# odd_v1.net
KiCad netlist of a schematic drawn in EAGLE
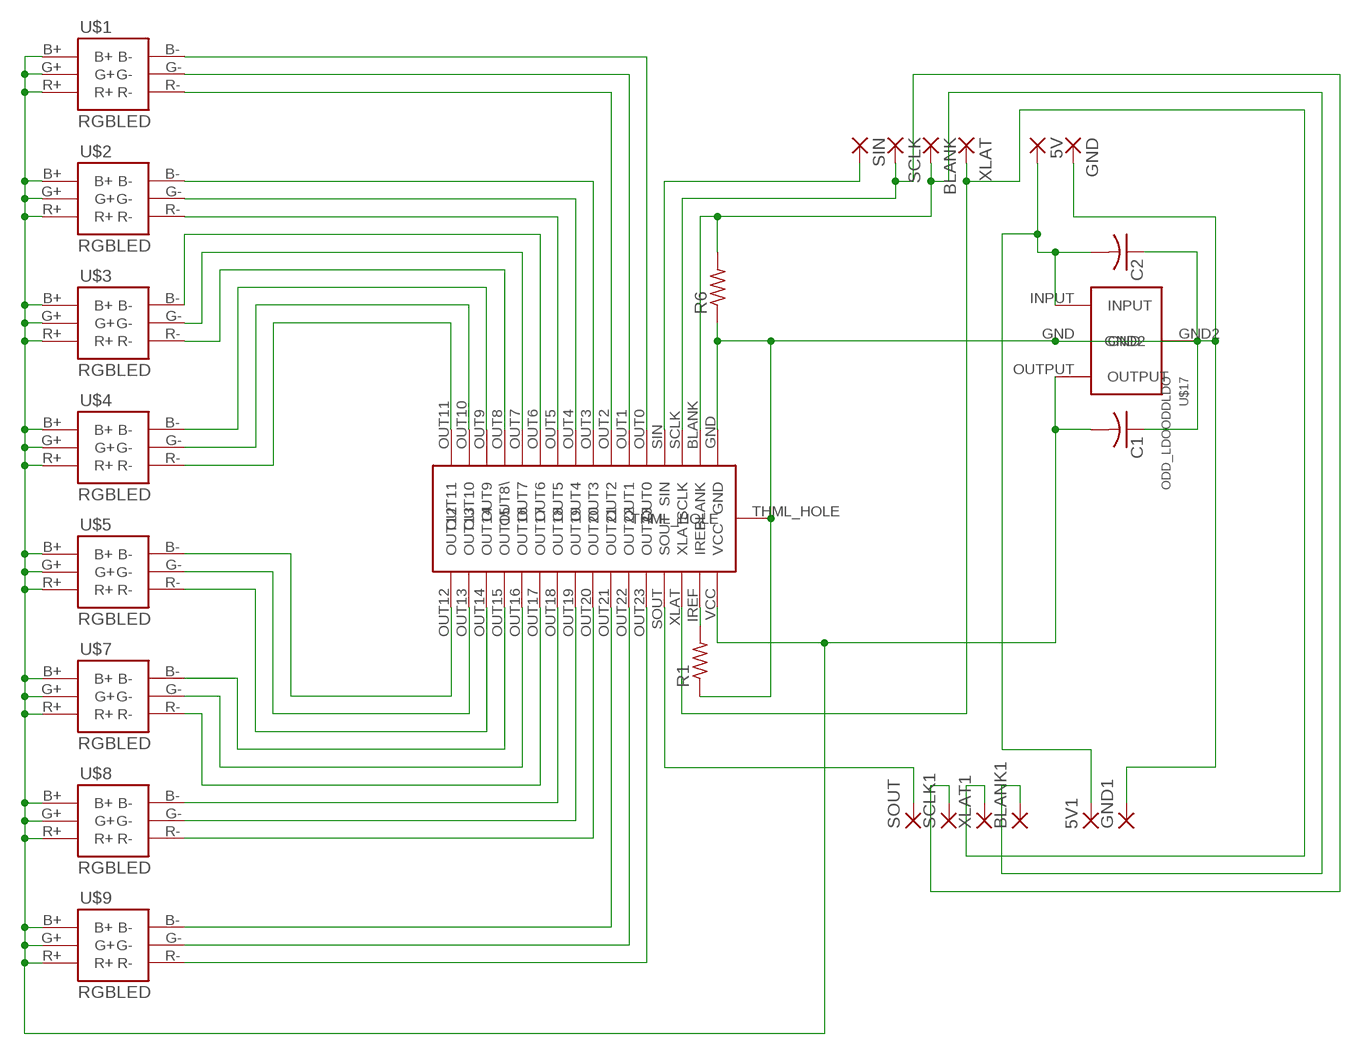
[diagram p0: schematic, sheet 1]

(export (version "E")
  (design (tool "Eeschema 10.0.6"))
  (components
    (comp (ref "5V")
      (value "2,54/1,1")
      (footprint "eagle-import:2,54_1,1")
      (libsource (lib "eagle-import") (part "2,54/1,1"))
    )
    (comp (ref "5V1")
      (value "2,54/1,1")
      (footprint "eagle-import:2,54_1,1")
      (libsource (lib "eagle-import") (part "2,54/1,1"))
    )
    (comp (ref "BLANK")
      (value "2,54/1,1")
      (footprint "eagle-import:2,54_1,1")
      (libsource (lib "eagle-import") (part "2,54/1,1"))
    )
    (comp (ref "BLANK1")
      (value "2,54/1,1")
      (footprint "eagle-import:2,54_1,1")
      (libsource (lib "eagle-import") (part "2,54/1,1"))
    )
    (comp (ref "C1")
      (value "C-US050-025X075")
      (footprint "eagle-import:C050-025X075")
      (libsource (lib "eagle-import") (part "C-US050-025X075"))
    )
    (comp (ref "C2")
      (value "C-US050-025X075")
      (footprint "eagle-import:C050-025X075")
      (libsource (lib "eagle-import") (part "C-US050-025X075"))
    )
    (comp (ref "GND")
      (value "2,54/1,1")
      (footprint "eagle-import:2,54_1,1")
      (libsource (lib "eagle-import") (part "2,54/1,1"))
    )
    (comp (ref "GND1")
      (value "2,54/1,1")
      (footprint "eagle-import:2,54_1,1")
      (libsource (lib "eagle-import") (part "2,54/1,1"))
    )
    (comp (ref "R1")
      (value "R-US_0204/7")
      (footprint "eagle-import:0204_7")
      (libsource (lib "eagle-import") (part "R-US_0204/7"))
    )
    (comp (ref "R6")
      (value "R-US_0204/7")
      (footprint "eagle-import:0204_7")
      (libsource (lib "eagle-import") (part "R-US_0204/7"))
    )
    (comp (ref "SCLK")
      (value "2,54/1,1")
      (footprint "eagle-import:2,54_1,1")
      (libsource (lib "eagle-import") (part "2,54/1,1"))
    )
    (comp (ref "SCLK1")
      (value "2,54/1,1")
      (footprint "eagle-import:2,54_1,1")
      (libsource (lib "eagle-import") (part "2,54/1,1"))
    )
    (comp (ref "SIN")
      (value "2,54/1,1")
      (footprint "eagle-import:2,54_1,1")
      (libsource (lib "eagle-import") (part "2,54/1,1"))
    )
    (comp (ref "SOUT")
      (value "2,54/1,1")
      (footprint "eagle-import:2,54_1,1")
      (libsource (lib "eagle-import") (part "2,54/1,1"))
    )
    (comp (ref "U$1")
      (value "RGBLED")
      (footprint "eagle-import:6PADSMD")
      (libsource (lib "eagle-import") (part "CREESMDRGBLED6PADSMD"))
    )
    (comp (ref "U$2")
      (value "RGBLED")
      (footprint "eagle-import:6PADSMD")
      (libsource (lib "eagle-import") (part "CREESMDRGBLED6PADSMD"))
    )
    (comp (ref "U$3")
      (value "RGBLED")
      (footprint "eagle-import:6PADSMD")
      (libsource (lib "eagle-import") (part "CREESMDRGBLED6PADSMD"))
    )
    (comp (ref "U$4")
      (value "RGBLED")
      (footprint "eagle-import:6PADSMD")
      (libsource (lib "eagle-import") (part "CREESMDRGBLED6PADSMD"))
    )
    (comp (ref "U$5")
      (value "RGBLED")
      (footprint "eagle-import:6PADSMD")
      (libsource (lib "eagle-import") (part "CREESMDRGBLED6PADSMD"))
    )
    (comp (ref "U$6")
      (value "TLC5947")
      (footprint "eagle-import:32_SMD")
      (libsource (lib "eagle-import") (part "TLC5947"))
    )
    (comp (ref "U$7")
      (value "RGBLED")
      (footprint "eagle-import:6PADSMD")
      (libsource (lib "eagle-import") (part "CREESMDRGBLED6PADSMD"))
    )
    (comp (ref "U$8")
      (value "RGBLED")
      (footprint "eagle-import:6PADSMD")
      (libsource (lib "eagle-import") (part "CREESMDRGBLED6PADSMD"))
    )
    (comp (ref "U$9")
      (value "RGBLED")
      (footprint "eagle-import:6PADSMD")
      (libsource (lib "eagle-import") (part "CREESMDRGBLED6PADSMD"))
    )
    (comp (ref "U$17")
      (value "ODD_LDOODDLDO")
      (footprint "eagle-import:4PINLDO")
      (libsource (lib "eagle-import") (part "ODD_LDOODDLDO"))
    )
    (comp (ref "XLAT")
      (value "2,54/1,1")
      (footprint "eagle-import:2,54_1,1")
      (libsource (lib "eagle-import") (part "2,54/1,1"))
    )
    (comp (ref "XLAT1")
      (value "2,54/1,1")
      (footprint "eagle-import:2,54_1,1")
      (libsource (lib "eagle-import") (part "2,54/1,1"))
    )
  )
  (nets
    (net (code "1") (name "Net-(5V-P)") (class "Default")
      (node (ref "5V") (pin "1") (pinfunction "P_1") (pintype "passive"))
      (node (ref "5V1") (pin "1") (pinfunction "P_1") (pintype "passive"))
      (node (ref "C2") (pin "2") (pinfunction "2_2") (pintype "passive"))
      (node (ref "U$17") (pin "INPUT") (pinfunction "INPUT_INPUT") (pintype "bidirectional"))
    )
    (net (code "2") (name "Net-(BLANK-P)") (class "Default")
      (node (ref "BLANK") (pin "1") (pinfunction "P_1") (pintype "passive"))
      (node (ref "BLANK1") (pin "1") (pinfunction "P_1") (pintype "passive"))
      (node (ref "R6") (pin "2") (pinfunction "2_2") (pintype "passive"))
      (node (ref "U$6") (pin "BLANK") (pinfunction "BLANK_BLANK") (pintype "bidirectional"))
    )
    (net (code "3") (name "Net-(C1-Pad2)") (class "Default")
      (node (ref "C1") (pin "2") (pinfunction "2_2") (pintype "passive"))
      (node (ref "U$1") (pin "B+") (pinfunction "B+_B+") (pintype "bidirectional"))
      (node (ref "U$1") (pin "G+") (pinfunction "G+_G+") (pintype "bidirectional"))
      (node (ref "U$1") (pin "R+") (pinfunction "R+_R+") (pintype "bidirectional"))
      (node (ref "U$17") (pin "OUTPUT") (pinfunction "OUTPUT_OUTPUT") (pintype "bidirectional"))
      (node (ref "U$2") (pin "B+") (pinfunction "B+_B+") (pintype "bidirectional"))
      (node (ref "U$2") (pin "G+") (pinfunction "G+_G+") (pintype "bidirectional"))
      (node (ref "U$2") (pin "R+") (pinfunction "R+_R+") (pintype "bidirectional"))
      (node (ref "U$3") (pin "B+") (pinfunction "B+_B+") (pintype "bidirectional"))
      (node (ref "U$3") (pin "G+") (pinfunction "G+_G+") (pintype "bidirectional"))
      (node (ref "U$3") (pin "R+") (pinfunction "R+_R+") (pintype "bidirectional"))
      (node (ref "U$4") (pin "B+") (pinfunction "B+_B+") (pintype "bidirectional"))
      (node (ref "U$4") (pin "G+") (pinfunction "G+_G+") (pintype "bidirectional"))
      (node (ref "U$4") (pin "R+") (pinfunction "R+_R+") (pintype "bidirectional"))
      (node (ref "U$5") (pin "B+") (pinfunction "B+_B+") (pintype "bidirectional"))
      (node (ref "U$5") (pin "G+") (pinfunction "G+_G+") (pintype "bidirectional"))
      (node (ref "U$5") (pin "R+") (pinfunction "R+_R+") (pintype "bidirectional"))
      (node (ref "U$6") (pin "VCC") (pinfunction "VCC_VCC") (pintype "bidirectional"))
      (node (ref "U$7") (pin "B+") (pinfunction "B+_B+") (pintype "bidirectional"))
      (node (ref "U$7") (pin "G+") (pinfunction "G+_G+") (pintype "bidirectional"))
      (node (ref "U$7") (pin "R+") (pinfunction "R+_R+") (pintype "bidirectional"))
      (node (ref "U$8") (pin "B+") (pinfunction "B+_B+") (pintype "bidirectional"))
      (node (ref "U$8") (pin "G+") (pinfunction "G+_G+") (pintype "bidirectional"))
      (node (ref "U$8") (pin "R+") (pinfunction "R+_R+") (pintype "bidirectional"))
      (node (ref "U$9") (pin "B+") (pinfunction "B+_B+") (pintype "bidirectional"))
      (node (ref "U$9") (pin "G+") (pinfunction "G+_G+") (pintype "bidirectional"))
      (node (ref "U$9") (pin "R+") (pinfunction "R+_R+") (pintype "bidirectional"))
    )
    (net (code "4") (name "Net-(GND-P)") (class "Default")
      (node (ref "C1") (pin "1") (pinfunction "1_1") (pintype "passive"))
      (node (ref "C2") (pin "1") (pinfunction "1_1") (pintype "passive"))
      (node (ref "GND") (pin "1") (pinfunction "P_1") (pintype "passive"))
      (node (ref "GND1") (pin "1") (pinfunction "P_1") (pintype "passive"))
      (node (ref "R1") (pin "1") (pinfunction "1_1") (pintype "passive"))
      (node (ref "R6") (pin "1") (pinfunction "1_1") (pintype "passive"))
      (node (ref "U$17") (pin "GND") (pinfunction "GND_GND") (pintype "bidirectional"))
      (node (ref "U$17") (pin "GND2") (pinfunction "GND2_GND2") (pintype "bidirectional"))
      (node (ref "U$6") (pin "GND") (pinfunction "GND_GND") (pintype "bidirectional"))
      (node (ref "U$6") (pin "THML_HOLE") (pinfunction "THML_HOLE_THML_HOLE") (pintype "bidirectional"))
    )
    (net (code "5") (name "Net-(R1-Pad2)") (class "Default")
      (node (ref "R1") (pin "2") (pinfunction "2_2") (pintype "passive"))
      (node (ref "U$6") (pin "IREF") (pinfunction "IREF_IREF") (pintype "bidirectional"))
    )
    (net (code "6") (name "Net-(SCLK-P)") (class "Default")
      (node (ref "SCLK") (pin "1") (pinfunction "P_1") (pintype "passive"))
      (node (ref "SCLK1") (pin "1") (pinfunction "P_1") (pintype "passive"))
      (node (ref "U$6") (pin "SCLK") (pinfunction "SCLK_SCLK") (pintype "bidirectional"))
    )
    (net (code "7") (name "Net-(SIN-P)") (class "Default")
      (node (ref "SIN") (pin "1") (pinfunction "P_1") (pintype "passive"))
      (node (ref "U$6") (pin "SIN") (pinfunction "SIN_SIN") (pintype "bidirectional"))
    )
    (net (code "8") (name "Net-(SOUT-P)") (class "Default")
      (node (ref "SOUT") (pin "1") (pinfunction "P_1") (pintype "passive"))
      (node (ref "U$6") (pin "SOUT") (pinfunction "SOUT_SOUT") (pintype "bidirectional"))
    )
    (net (code "9") (name "Net-(U$1-PadB-)") (class "Default")
      (node (ref "U$1") (pin "B-") (pinfunction "B-_B-") (pintype "bidirectional"))
      (node (ref "U$6") (pin "OUT0") (pinfunction "OUT0_OUT0") (pintype "bidirectional"))
    )
    (net (code "10") (name "Net-(U$1-PadG-)") (class "Default")
      (node (ref "U$1") (pin "G-") (pinfunction "G-_G-") (pintype "bidirectional"))
      (node (ref "U$6") (pin "OUT1") (pinfunction "OUT1_OUT1") (pintype "bidirectional"))
    )
    (net (code "11") (name "Net-(U$1-PadR-)") (class "Default")
      (node (ref "U$1") (pin "R-") (pinfunction "R-_R-") (pintype "bidirectional"))
      (node (ref "U$6") (pin "OUT2") (pinfunction "OUT2_OUT2") (pintype "bidirectional"))
    )
    (net (code "12") (name "Net-(U$2-PadB-)") (class "Default")
      (node (ref "U$2") (pin "B-") (pinfunction "B-_B-") (pintype "bidirectional"))
      (node (ref "U$6") (pin "OUT3") (pinfunction "OUT3_OUT3") (pintype "bidirectional"))
    )
    (net (code "13") (name "Net-(U$2-PadG-)") (class "Default")
      (node (ref "U$2") (pin "G-") (pinfunction "G-_G-") (pintype "bidirectional"))
      (node (ref "U$6") (pin "OUT4") (pinfunction "OUT4_OUT4") (pintype "bidirectional"))
    )
    (net (code "14") (name "Net-(U$2-PadR-)") (class "Default")
      (node (ref "U$2") (pin "R-") (pinfunction "R-_R-") (pintype "bidirectional"))
      (node (ref "U$6") (pin "OUT5") (pinfunction "OUT5_OUT5") (pintype "bidirectional"))
    )
    (net (code "15") (name "Net-(U$3-PadB-)") (class "Default")
      (node (ref "U$3") (pin "B-") (pinfunction "B-_B-") (pintype "bidirectional"))
      (node (ref "U$6") (pin "OUT6") (pinfunction "OUT6_OUT6") (pintype "bidirectional"))
    )
    (net (code "16") (name "Net-(U$3-PadG-)") (class "Default")
      (node (ref "U$3") (pin "G-") (pinfunction "G-_G-") (pintype "bidirectional"))
      (node (ref "U$6") (pin "OUT7") (pinfunction "OUT7_OUT7") (pintype "bidirectional"))
    )
    (net (code "17") (name "Net-(U$4-PadB-)") (class "Default")
      (node (ref "U$4") (pin "B-") (pinfunction "B-_B-") (pintype "bidirectional"))
      (node (ref "U$6") (pin "OUT9") (pinfunction "OUT9_OUT9") (pintype "bidirectional"))
    )
    (net (code "18") (name "Net-(U$4-PadG-)") (class "Default")
      (node (ref "U$4") (pin "G-") (pinfunction "G-_G-") (pintype "bidirectional"))
      (node (ref "U$6") (pin "OUT10") (pinfunction "OUT10_OUT10") (pintype "bidirectional"))
    )
    (net (code "19") (name "Net-(U$4-PadR-)") (class "Default")
      (node (ref "U$4") (pin "R-") (pinfunction "R-_R-") (pintype "bidirectional"))
      (node (ref "U$6") (pin "OUT11") (pinfunction "OUT11_OUT11") (pintype "bidirectional"))
    )
    (net (code "20") (name "Net-(U$5-PadB-)") (class "Default")
      (node (ref "U$5") (pin "B-") (pinfunction "B-_B-") (pintype "bidirectional"))
      (node (ref "U$6") (pin "OUT12") (pinfunction "OUT12_OUT12") (pintype "bidirectional"))
    )
    (net (code "21") (name "Net-(U$5-PadG-)") (class "Default")
      (node (ref "U$5") (pin "G-") (pinfunction "G-_G-") (pintype "bidirectional"))
      (node (ref "U$6") (pin "OUT13") (pinfunction "OUT13_OUT13") (pintype "bidirectional"))
    )
    (net (code "22") (name "Net-(U$5-PadR-)") (class "Default")
      (node (ref "U$5") (pin "R-") (pinfunction "R-_R-") (pintype "bidirectional"))
      (node (ref "U$6") (pin "OUT14") (pinfunction "OUT14_OUT14") (pintype "bidirectional"))
    )
    (net (code "23") (name "Net-(U$6-OUT8\\)") (class "Default")
      (node (ref "U$3") (pin "R-") (pinfunction "R-_R-") (pintype "bidirectional"))
      (node (ref "U$6") (pin "OUT8") (pinfunction "OUT8\\_OUT8") (pintype "bidirectional"))
    )
    (net (code "24") (name "Net-(U$6-PadOUT15)") (class "Default")
      (node (ref "U$6") (pin "OUT15") (pinfunction "OUT15_OUT15") (pintype "bidirectional"))
      (node (ref "U$7") (pin "B-") (pinfunction "B-_B-") (pintype "bidirectional"))
    )
    (net (code "25") (name "Net-(U$6-PadOUT16)") (class "Default")
      (node (ref "U$6") (pin "OUT16") (pinfunction "OUT16_OUT16") (pintype "bidirectional"))
      (node (ref "U$7") (pin "G-") (pinfunction "G-_G-") (pintype "bidirectional"))
    )
    (net (code "26") (name "Net-(U$6-PadOUT17)") (class "Default")
      (node (ref "U$6") (pin "OUT17") (pinfunction "OUT17_OUT17") (pintype "bidirectional"))
      (node (ref "U$7") (pin "R-") (pinfunction "R-_R-") (pintype "bidirectional"))
    )
    (net (code "27") (name "Net-(U$6-PadOUT18)") (class "Default")
      (node (ref "U$6") (pin "OUT18") (pinfunction "OUT18_OUT18") (pintype "bidirectional"))
      (node (ref "U$8") (pin "B-") (pinfunction "B-_B-") (pintype "bidirectional"))
    )
    (net (code "28") (name "Net-(U$6-PadOUT19)") (class "Default")
      (node (ref "U$6") (pin "OUT19") (pinfunction "OUT19_OUT19") (pintype "bidirectional"))
      (node (ref "U$8") (pin "G-") (pinfunction "G-_G-") (pintype "bidirectional"))
    )
    (net (code "29") (name "Net-(U$6-PadOUT20)") (class "Default")
      (node (ref "U$6") (pin "OUT20") (pinfunction "OUT20_OUT20") (pintype "bidirectional"))
      (node (ref "U$8") (pin "R-") (pinfunction "R-_R-") (pintype "bidirectional"))
    )
    (net (code "30") (name "Net-(U$6-PadOUT21)") (class "Default")
      (node (ref "U$6") (pin "OUT21") (pinfunction "OUT21_OUT21") (pintype "bidirectional"))
      (node (ref "U$9") (pin "B-") (pinfunction "B-_B-") (pintype "bidirectional"))
    )
    (net (code "31") (name "Net-(U$6-PadOUT22)") (class "Default")
      (node (ref "U$6") (pin "OUT22") (pinfunction "OUT22_OUT22") (pintype "bidirectional"))
      (node (ref "U$9") (pin "G-") (pinfunction "G-_G-") (pintype "bidirectional"))
    )
    (net (code "32") (name "Net-(U$6-PadOUT23)") (class "Default")
      (node (ref "U$6") (pin "OUT23") (pinfunction "OUT23_OUT23") (pintype "bidirectional"))
      (node (ref "U$9") (pin "R-") (pinfunction "R-_R-") (pintype "bidirectional"))
    )
    (net (code "33") (name "Net-(XLAT-P)") (class "Default")
      (node (ref "U$6") (pin "XLAT") (pinfunction "XLAT_XLAT") (pintype "bidirectional"))
      (node (ref "XLAT") (pin "1") (pinfunction "P_1") (pintype "passive"))
      (node (ref "XLAT1") (pin "1") (pinfunction "P_1") (pintype "passive"))
    )
  )
)
